# MCU.net
KiCad netlist of a schematic drawn in Altium Designer
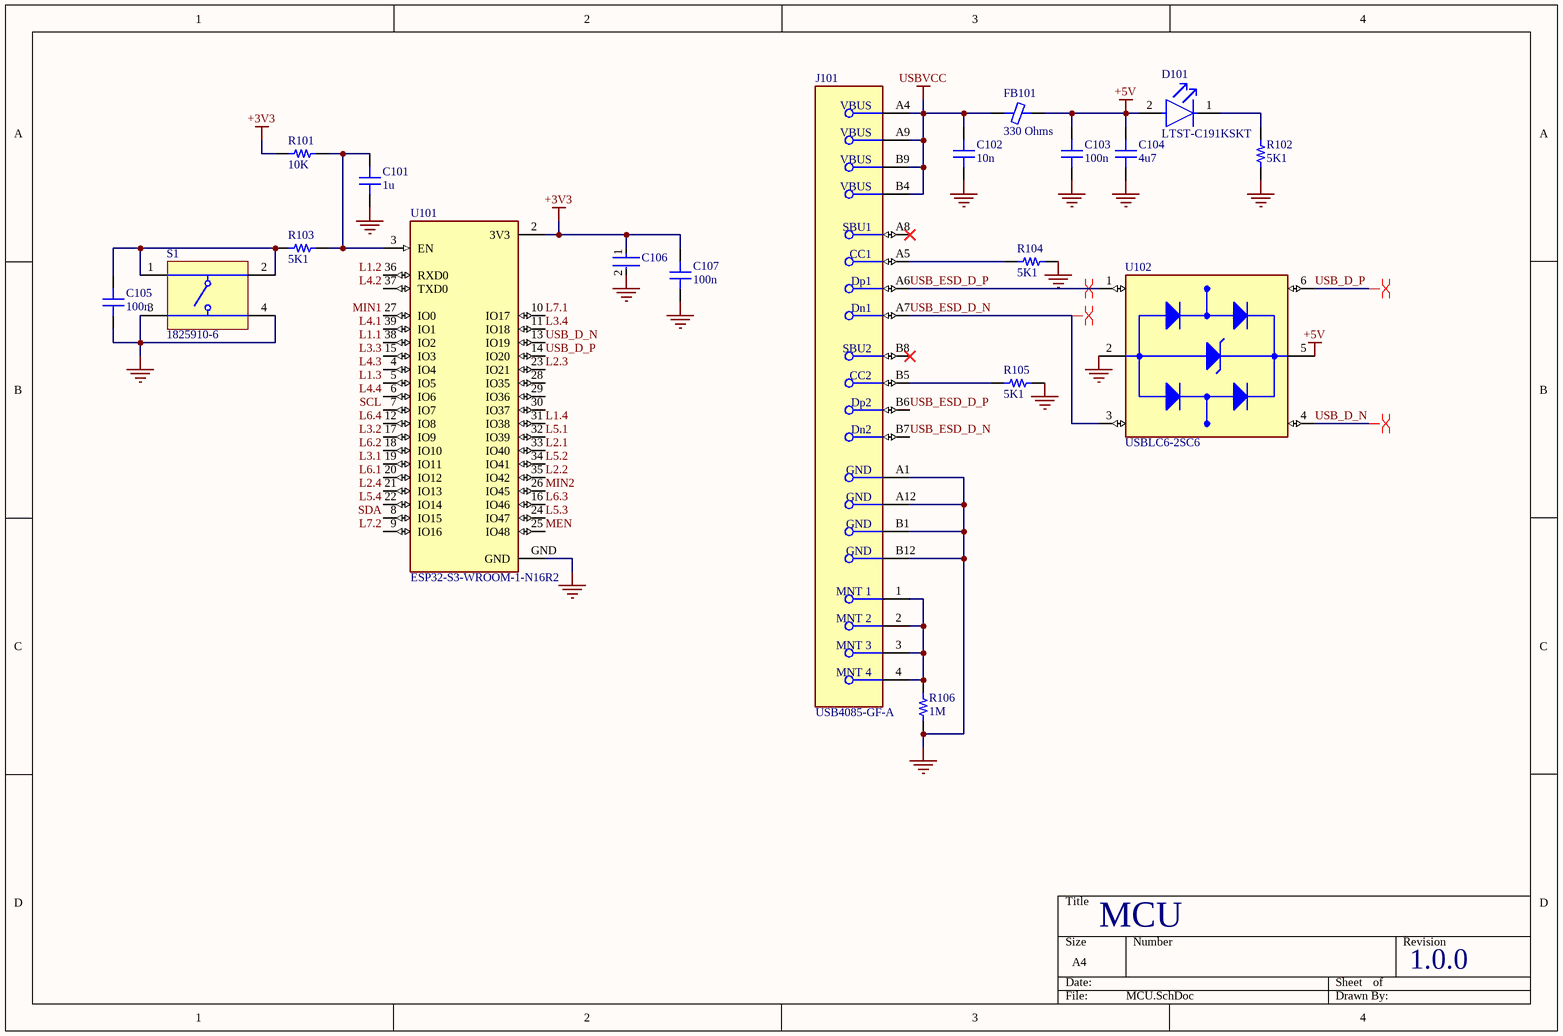
[diagram p0: MCU.SchDoc]

(export (version "E")
  (design (tool "Eeschema 10.0.6"))
  (components
    (comp (ref "C101")
      (value "1u")
      (footprint "CAP 0402_1005")
      (description "CAP CER 100NF 10V X7R 0402")
      (fields
        (field (name "PART NUMBER") "CL05B104KP5VPNC")
        (field (name "MANUFACTURER") "Samsung Electro-Mechanics")
      )
      (libsource (lib "Celestial Altium Library - altium_library") (part "Capacitor"))
    )
    (comp (ref "C102")
      (value "10n")
      (footprint "CAP 0402_1005")
      (description "CAP CER 100NF 10V X7R 0402")
      (fields
        (field (name "PART NUMBER") "CL05B104KP5VPNC")
        (field (name "MANUFACTURER") "Samsung Electro-Mechanics")
      )
      (libsource (lib "Celestial Altium Library - altium_library") (part "Capacitor"))
    )
    (comp (ref "C103")
      (value "100n")
      (footprint "CAP 0402_1005")
      (description "CAP CER 100NF 10V X7R 0402")
      (fields
        (field (name "PART NUMBER") "CL05B104KP5VPNC")
        (field (name "MANUFACTURER") "Samsung Electro-Mechanics")
      )
      (libsource (lib "Celestial Altium Library - altium_library") (part "Capacitor"))
    )
    (comp (ref "C104")
      (value "4u7")
      (footprint "CAP 0603_1608")
      (description "CAP CER 4.7UF 25V X5R 0603")
      (fields
        (field (name "PART NUMBER") "CL10A475KA8NQNC")
        (field (name "MANUFACTURER") "Samsung Electro-Mechanics")
      )
      (libsource (lib "Celestial Altium Library - altium_library") (part "Capacitor"))
    )
    (comp (ref "C105")
      (value "100n")
      (footprint "CAP 0402_1005")
      (description "CAP CER 100NF 10V X7R 0402")
      (fields
        (field (name "PART NUMBER") "CL05B104KP5VPNC")
        (field (name "MANUFACTURER") "Samsung Electro-Mechanics")
      )
      (libsource (lib "Celestial Altium Library - altium_library") (part "Capacitor"))
    )
    (comp (ref "C106")
      (value "C2012X5R1V226M125AC")
      (footprint "FP-C2012-125-0_2-IPC_C")
      (description "Multilayer Ceramic Capacitors 22μF ±20% 35V X5R SMD 0805")
      (fields (field (name "TOLERANCE") "20%"))
      (libsource (lib "Altium Content Vault") (part "b4654b650e69147ec39a6b967a45e02"))
    )
    (comp (ref "C107")
      (value "100n")
      (footprint "CAP 0402_1005")
      (description "CAP CER 100NF 10V X7R 0402")
      (fields
        (field (name "PART NUMBER") "CL05B104KP5VPNC")
        (field (name "MANUFACTURER") "Samsung Electro-Mechanics")
      )
      (libsource (lib "Celestial Altium Library - altium_library") (part "Capacitor"))
    )
    (comp (ref "D101")
      (value "LTST-C191KSKT")
      (footprint "FP-LTST-C191KSKT-MFG")
      (description "LED YELLOW CLEAR SMD")
      (libsource (lib "Altium Content Vault") (part "8706943c75ba83719d021d2fdc84c58"))
    )
    (comp (ref "FB101")
      (value "330 Ohms")
      (footprint "FER 0402_1005")
      (description "FERRITE BEAD 120 OHM 0402 1LN")
      (fields (field (name "PART NUMBER") "Z0402C121ASMST") (field (name "MANUFACTURER") "KEMET"))
      (libsource (lib "Celestial Altium Library - altium_library") (part "Ferrite Chip"))
    )
    (comp (ref "J101")
      (value "USB4085-GF-A")
      (footprint "FP-USB4085-GF-A-MFG")
      (description "CONN RCPT USB2.0 TYPE C 24POS RA")
      (libsource (lib "Altium Content Vault") (part "10fa745527c8b974685cbca3c197132"))
    )
    (comp (ref "R101")
      (value "10K")
      (footprint "RES 0402_1005")
      (description "RES SMD 5.1K OHM 5% 1/16W 0402")
      (fields (field (name "PART NUMBER") "AC0402JR-075K1L") (field (name "MANUFACTURER") "Yageo"))
      (libsource (lib "Celestial Altium Library - altium_library") (part "Resistor"))
    )
    (comp (ref "R102")
      (value "5K1")
      (footprint "RES 0402_1005")
      (description "RES SMD 5.1K OHM 5% 1/16W 0402")
      (fields (field (name "PART NUMBER") "AC0402JR-075K1L") (field (name "MANUFACTURER") "Yageo"))
      (libsource (lib "Celestial Altium Library - altium_library") (part "Resistor"))
    )
    (comp (ref "R103")
      (value "5K1")
      (footprint "RES 0402_1005")
      (description "RES SMD 5.1K OHM 5% 1/16W 0402")
      (fields (field (name "PART NUMBER") "AC0402JR-075K1L") (field (name "MANUFACTURER") "Yageo"))
      (libsource (lib "Celestial Altium Library - altium_library") (part "Resistor"))
    )
    (comp (ref "R104")
      (value "5K1")
      (footprint "RES 0402_1005")
      (description "RES SMD 5.1K OHM 5% 1/16W 0402")
      (fields (field (name "PART NUMBER") "AC0402JR-075K1L") (field (name "MANUFACTURER") "Yageo"))
      (libsource (lib "Celestial Altium Library - altium_library") (part "Resistor"))
    )
    (comp (ref "R105")
      (value "5K1")
      (footprint "RES 0402_1005")
      (description "RES SMD 5.1K OHM 5% 1/16W 0402")
      (fields (field (name "PART NUMBER") "AC0402JR-075K1L") (field (name "MANUFACTURER") "Yageo"))
      (libsource (lib "Celestial Altium Library - altium_library") (part "Resistor"))
    )
    (comp (ref "R106")
      (value "1M")
      (footprint "RES 0402_1005")
      (description "RES SMD 5.1K OHM 5% 1/16W 0402")
      (fields (field (name "PART NUMBER") "AC0402JR-075K1L") (field (name "MANUFACTURER") "Yageo"))
      (libsource (lib "Celestial Altium Library - altium_library") (part "Resistor"))
    )
    (comp (ref "S1")
      (value "1825910-6")
      (footprint "TECO-1825910-6_V")
      (description "Tact Switch, SPST-NO, 0.05 A, -35 to 85 degC, 4-Pin THD, RoHS, Bulk")
      (fields (field (name "MANUFACTURER") "TE Connectivity"))
      (libsource (lib "Altium Content Vault") (part "SW-SPST-4_A"))
    )
    (comp (ref "U101")
      (value "ESP32-S3-WROOM-1-N16R2")
      (footprint "XCVR_ESP32-S3-WROOM-1-N16R2")
      (description "Bluetooth, WiFi 802.11b/g/n, Bluetooth v5.0 Transceiver Module 2.4GHz PCB Trace Surface Mount")
      (fields (field (name "MF") "Espressif Systems") (field (name "MP") "ESP32S3WROOM1N16R2"))
      (libsource (lib "ESP32-S3-WROOM-1-N16R2") (part "ESP32-S3-WROOM-1-N16R2"))
    )
    (comp (ref "U102")
      (value "USBLC6-2SC6")
      (footprint "SOT95P280X145-6N")
      (description "17V Clamp 5A (8/20Âµs) Ipp Tvs Diode Surface Mount SOT-23-6")
      (fields (field (name "MF") "STMicroelectronics"))
      (libsource (lib "USBLC6-2SC6") (part "USBLC6-2SC6"))
    )
  )
  (nets
    (net (code "1") (name "+3V3") (class "Default")
      (node (ref "C106") (pin "1") (pinfunction "1_1") (pintype "passive"))
      (node (ref "C107") (pin "2") (pinfunction "2_2") (pintype "passive"))
      (node (ref "R101") (pin "2") (pinfunction "2_2") (pintype "passive"))
      (node (ref "U101") (pin "2") (pinfunction "3V3_2") (pintype "power_in"))
    )
    (net (code "2") (name "+5V") (class "Default")
      (node (ref "C103") (pin "2") (pinfunction "2_2") (pintype "passive"))
      (node (ref "C104") (pin "2") (pinfunction "2_2") (pintype "passive"))
      (node (ref "D101") (pin "2") (pinfunction "A_2") (pintype "passive"))
      (node (ref "FB101") (pin "2") (pinfunction "2_2") (pintype "passive"))
      (node (ref "U102") (pin "5") (pinfunction "VBUS_5") (pintype "power_in"))
    )
    (net (code "3") (name "/L1.1") (class "Default")
      (node (ref "U101") (pin "38") (pinfunction "IO2_38") (pintype "bidirectional"))
    )
    (net (code "4") (name "/L1.2") (class "Default")
      (node (ref "U101") (pin "36") (pinfunction "RXD0_36") (pintype "bidirectional"))
    )
    (net (code "5") (name "/L1.3") (class "Default")
      (node (ref "U101") (pin "5") (pinfunction "IO5_5") (pintype "bidirectional"))
    )
    (net (code "6") (name "/L1.4") (class "Default")
      (node (ref "U101") (pin "31") (pinfunction "IO38_31") (pintype "bidirectional"))
    )
    (net (code "7") (name "/L2.1") (class "Default")
      (node (ref "U101") (pin "33") (pinfunction "IO40_33") (pintype "bidirectional"))
    )
    (net (code "8") (name "/L2.2") (class "Default")
      (node (ref "U101") (pin "35") (pinfunction "IO42_35") (pintype "bidirectional"))
    )
    (net (code "9") (name "/L2.3") (class "Default")
      (node (ref "U101") (pin "23") (pinfunction "IO21_23") (pintype "bidirectional"))
    )
    (net (code "10") (name "/L2.4") (class "Default")
      (node (ref "U101") (pin "21") (pinfunction "IO13_21") (pintype "bidirectional"))
    )
    (net (code "11") (name "/L3.1") (class "Default")
      (node (ref "U101") (pin "19") (pinfunction "IO11_19") (pintype "bidirectional"))
    )
    (net (code "12") (name "/L3.2") (class "Default")
      (node (ref "U101") (pin "17") (pinfunction "IO9_17") (pintype "bidirectional"))
    )
    (net (code "13") (name "/L3.3") (class "Default")
      (node (ref "U101") (pin "15") (pinfunction "IO3_15") (pintype "bidirectional"))
    )
    (net (code "14") (name "/L3.4") (class "Default")
      (node (ref "U101") (pin "11") (pinfunction "IO18_11") (pintype "bidirectional"))
    )
    (net (code "15") (name "/L4.1") (class "Default")
      (node (ref "U101") (pin "39") (pinfunction "IO1_39") (pintype "bidirectional"))
    )
    (net (code "16") (name "/L4.2") (class "Default")
      (node (ref "U101") (pin "37") (pinfunction "TXD0_37") (pintype "bidirectional"))
    )
    (net (code "17") (name "/L4.3") (class "Default")
      (node (ref "U101") (pin "4") (pinfunction "IO4_4") (pintype "bidirectional"))
    )
    (net (code "18") (name "/L4.4") (class "Default")
      (node (ref "U101") (pin "6") (pinfunction "IO6_6") (pintype "bidirectional"))
    )
    (net (code "19") (name "/L5.1") (class "Default")
      (node (ref "U101") (pin "32") (pinfunction "IO39_32") (pintype "bidirectional"))
    )
    (net (code "20") (name "/L5.2") (class "Default")
      (node (ref "U101") (pin "34") (pinfunction "IO41_34") (pintype "bidirectional"))
    )
    (net (code "21") (name "/L5.3") (class "Default")
      (node (ref "U101") (pin "24") (pinfunction "IO47_24") (pintype "bidirectional"))
    )
    (net (code "22") (name "/L5.4") (class "Default")
      (node (ref "U101") (pin "22") (pinfunction "IO14_22") (pintype "bidirectional"))
    )
    (net (code "23") (name "/L6.1") (class "Default")
      (node (ref "U101") (pin "20") (pinfunction "IO12_20") (pintype "bidirectional"))
    )
    (net (code "24") (name "/L6.2") (class "Default")
      (node (ref "U101") (pin "18") (pinfunction "IO10_18") (pintype "bidirectional"))
    )
    (net (code "25") (name "/L6.3") (class "Default")
      (node (ref "U101") (pin "16") (pinfunction "IO46_16") (pintype "bidirectional"))
    )
    (net (code "26") (name "/L6.4") (class "Default")
      (node (ref "U101") (pin "12") (pinfunction "IO8_12") (pintype "bidirectional"))
    )
    (net (code "27") (name "/L7.1") (class "Default")
      (node (ref "U101") (pin "10") (pinfunction "IO17_10") (pintype "bidirectional"))
    )
    (net (code "28") (name "/L7.2") (class "Default")
      (node (ref "U101") (pin "9") (pinfunction "IO16_9") (pintype "bidirectional"))
    )
    (net (code "29") (name "/MEN") (class "Default")
      (node (ref "U101") (pin "25") (pinfunction "IO48_25") (pintype "bidirectional"))
    )
    (net (code "30") (name "/MIN1") (class "Default")
      (node (ref "U101") (pin "27") (pinfunction "IO0_27") (pintype "bidirectional"))
    )
    (net (code "31") (name "/MIN2") (class "Default")
      (node (ref "U101") (pin "26") (pinfunction "IO45_26") (pintype "bidirectional"))
    )
    (net (code "32") (name "/SCL") (class "Default")
      (node (ref "U101") (pin "7") (pinfunction "IO7_7") (pintype "bidirectional"))
    )
    (net (code "33") (name "/SDA") (class "Default")
      (node (ref "U101") (pin "8") (pinfunction "IO15_8") (pintype "bidirectional"))
    )
    (net (code "34") (name "/USB_D_N") (class "Default")
      (node (ref "U101") (pin "13") (pinfunction "IO19_13") (pintype "bidirectional"))
      (node (ref "U102") (pin "4") (pinfunction "I/O2_OUT_4") (pintype "bidirectional"))
    )
    (net (code "35") (name "/USB_D_P") (class "Default")
      (node (ref "U101") (pin "14") (pinfunction "IO20_14") (pintype "bidirectional"))
      (node (ref "U102") (pin "6") (pinfunction "I/O1_OUT_6") (pintype "bidirectional"))
    )
    (net (code "36") (name "/USB_ESD_D_N") (class "Default")
      (node (ref "J101") (pin "A7") (pinfunction "Dn1_A7") (pintype "bidirectional"))
      (node (ref "J101") (pin "B7") (pinfunction "Dn2_B7") (pintype "bidirectional"))
      (node (ref "U102") (pin "3") (pinfunction "I/O2_IN_3") (pintype "bidirectional"))
    )
    (net (code "37") (name "/USB_ESD_D_P") (class "Default")
      (node (ref "J101") (pin "A6") (pinfunction "Dp1_A6") (pintype "bidirectional"))
      (node (ref "J101") (pin "B6") (pinfunction "Dp2_B6") (pintype "bidirectional"))
      (node (ref "U102") (pin "1") (pinfunction "I/O1_IN_1") (pintype "bidirectional"))
    )
    (net (code "38") (name "GND") (class "Default")
      (node (ref "C101") (pin "1") (pinfunction "1_1") (pintype "passive"))
      (node (ref "C102") (pin "1") (pinfunction "1_1") (pintype "passive"))
      (node (ref "C103") (pin "1") (pinfunction "1_1") (pintype "passive"))
      (node (ref "C104") (pin "1") (pinfunction "1_1") (pintype "passive"))
      (node (ref "C105") (pin "1") (pinfunction "1_1") (pintype "passive"))
      (node (ref "C106") (pin "2") (pinfunction "2_2") (pintype "passive"))
      (node (ref "C107") (pin "1") (pinfunction "1_1") (pintype "passive"))
      (node (ref "J101") (pin "A1") (pinfunction "GND_A1") (pintype "power_in"))
      (node (ref "J101") (pin "A12") (pinfunction "GND_A12") (pintype "power_in"))
      (node (ref "J101") (pin "B1") (pinfunction "GND_B1") (pintype "power_in"))
      (node (ref "J101") (pin "B12") (pinfunction "GND_B12") (pintype "power_in"))
      (node (ref "R102") (pin "1") (pinfunction "1_1") (pintype "passive"))
      (node (ref "R104") (pin "1") (pinfunction "1_1") (pintype "passive"))
      (node (ref "R105") (pin "1") (pinfunction "1_1") (pintype "passive"))
      (node (ref "R106") (pin "1") (pinfunction "1_1") (pintype "passive"))
      (node (ref "S1") (pin "3") (pinfunction "3_3") (pintype "passive"))
      (node (ref "S1") (pin "4") (pinfunction "4_4") (pintype "passive"))
      (node (ref "U101") (pin "GND") (pinfunction "GND_GND") (pintype "power_in"))
      (node (ref "U102") (pin "2") (pinfunction "GND_2") (pintype "power_in"))
    )
    (net (code "39") (name "Net-(C105-Pad2)") (class "Default")
      (node (ref "C105") (pin "2") (pinfunction "2_2") (pintype "passive"))
      (node (ref "R103") (pin "2") (pinfunction "2_2") (pintype "passive"))
      (node (ref "S1") (pin "1") (pinfunction "1_1") (pintype "passive"))
      (node (ref "S1") (pin "2") (pinfunction "2_2") (pintype "passive"))
    )
    (net (code "40") (name "Net-(D101-C)") (class "Default")
      (node (ref "D101") (pin "1") (pinfunction "C_1") (pintype "passive"))
      (node (ref "R102") (pin "2") (pinfunction "2_2") (pintype "passive"))
    )
    (net (code "41") (name "Net-(J101-CC1)") (class "Default")
      (node (ref "J101") (pin "A5") (pinfunction "CC1_A5") (pintype "bidirectional"))
      (node (ref "R104") (pin "2") (pinfunction "2_2") (pintype "passive"))
    )
    (net (code "42") (name "Net-(J101-CC2)") (class "Default")
      (node (ref "J101") (pin "B5") (pinfunction "CC2_B5") (pintype "bidirectional"))
      (node (ref "R105") (pin "2") (pinfunction "2_2") (pintype "passive"))
    )
    (net (code "43") (name "Net-(J101-MNT_1)") (class "Default")
      (node (ref "J101") (pin "1") (pinfunction "MNT_1_1") (pintype "passive"))
      (node (ref "J101") (pin "2") (pinfunction "MNT_2_2") (pintype "passive"))
      (node (ref "J101") (pin "3") (pinfunction "MNT_3_3") (pintype "passive"))
      (node (ref "J101") (pin "4") (pinfunction "MNT_4_4") (pintype "passive"))
      (node (ref "R106") (pin "2") (pinfunction "2_2") (pintype "passive"))
    )
    (net (code "44") (name "Net-(U101-EN)") (class "Default")
      (node (ref "C101") (pin "2") (pinfunction "2_2") (pintype "passive"))
      (node (ref "R101") (pin "1") (pinfunction "1_1") (pintype "passive"))
      (node (ref "R103") (pin "1") (pinfunction "1_1") (pintype "passive"))
      (node (ref "U101") (pin "3") (pinfunction "EN_3") (pintype "input"))
    )
    (net (code "45") (name "USBVCC") (class "Default")
      (node (ref "C102") (pin "2") (pinfunction "2_2") (pintype "passive"))
      (node (ref "FB101") (pin "1") (pinfunction "1_1") (pintype "passive"))
      (node (ref "J101") (pin "A4") (pinfunction "VBUS_A4") (pintype "power_in"))
      (node (ref "J101") (pin "A9") (pinfunction "VBUS_A9") (pintype "power_in"))
      (node (ref "J101") (pin "B4") (pinfunction "VBUS_B4") (pintype "power_in"))
      (node (ref "J101") (pin "B9") (pinfunction "VBUS_B9") (pintype "power_in"))
    )
    (net (code "46") (name "unconnected-(J101-SBU1-PadA8)") (class "Default")
      (node (ref "J101") (pin "A8") (pinfunction "SBU1_A8") (pintype "bidirectional+no_connect"))
    )
    (net (code "47") (name "unconnected-(J101-SBU2-PadB8)") (class "Default")
      (node (ref "J101") (pin "B8") (pinfunction "SBU2_B8") (pintype "bidirectional+no_connect"))
    )
    (net (code "48") (name "unconnected-(U101-IO35-Pad28)") (class "Default")
      (node (ref "U101") (pin "28") (pinfunction "IO35_28") (pintype "bidirectional"))
    )
    (net (code "49") (name "unconnected-(U101-IO36-Pad29)") (class "Default")
      (node (ref "U101") (pin "29") (pinfunction "IO36_29") (pintype "bidirectional"))
    )
    (net (code "50") (name "unconnected-(U101-IO37-Pad30)") (class "Default")
      (node (ref "U101") (pin "30") (pinfunction "IO37_30") (pintype "bidirectional"))
    )
  )
)
